# BPW5011-Digital-Wing.net
KiCad netlist of a schematic drawn in EAGLE
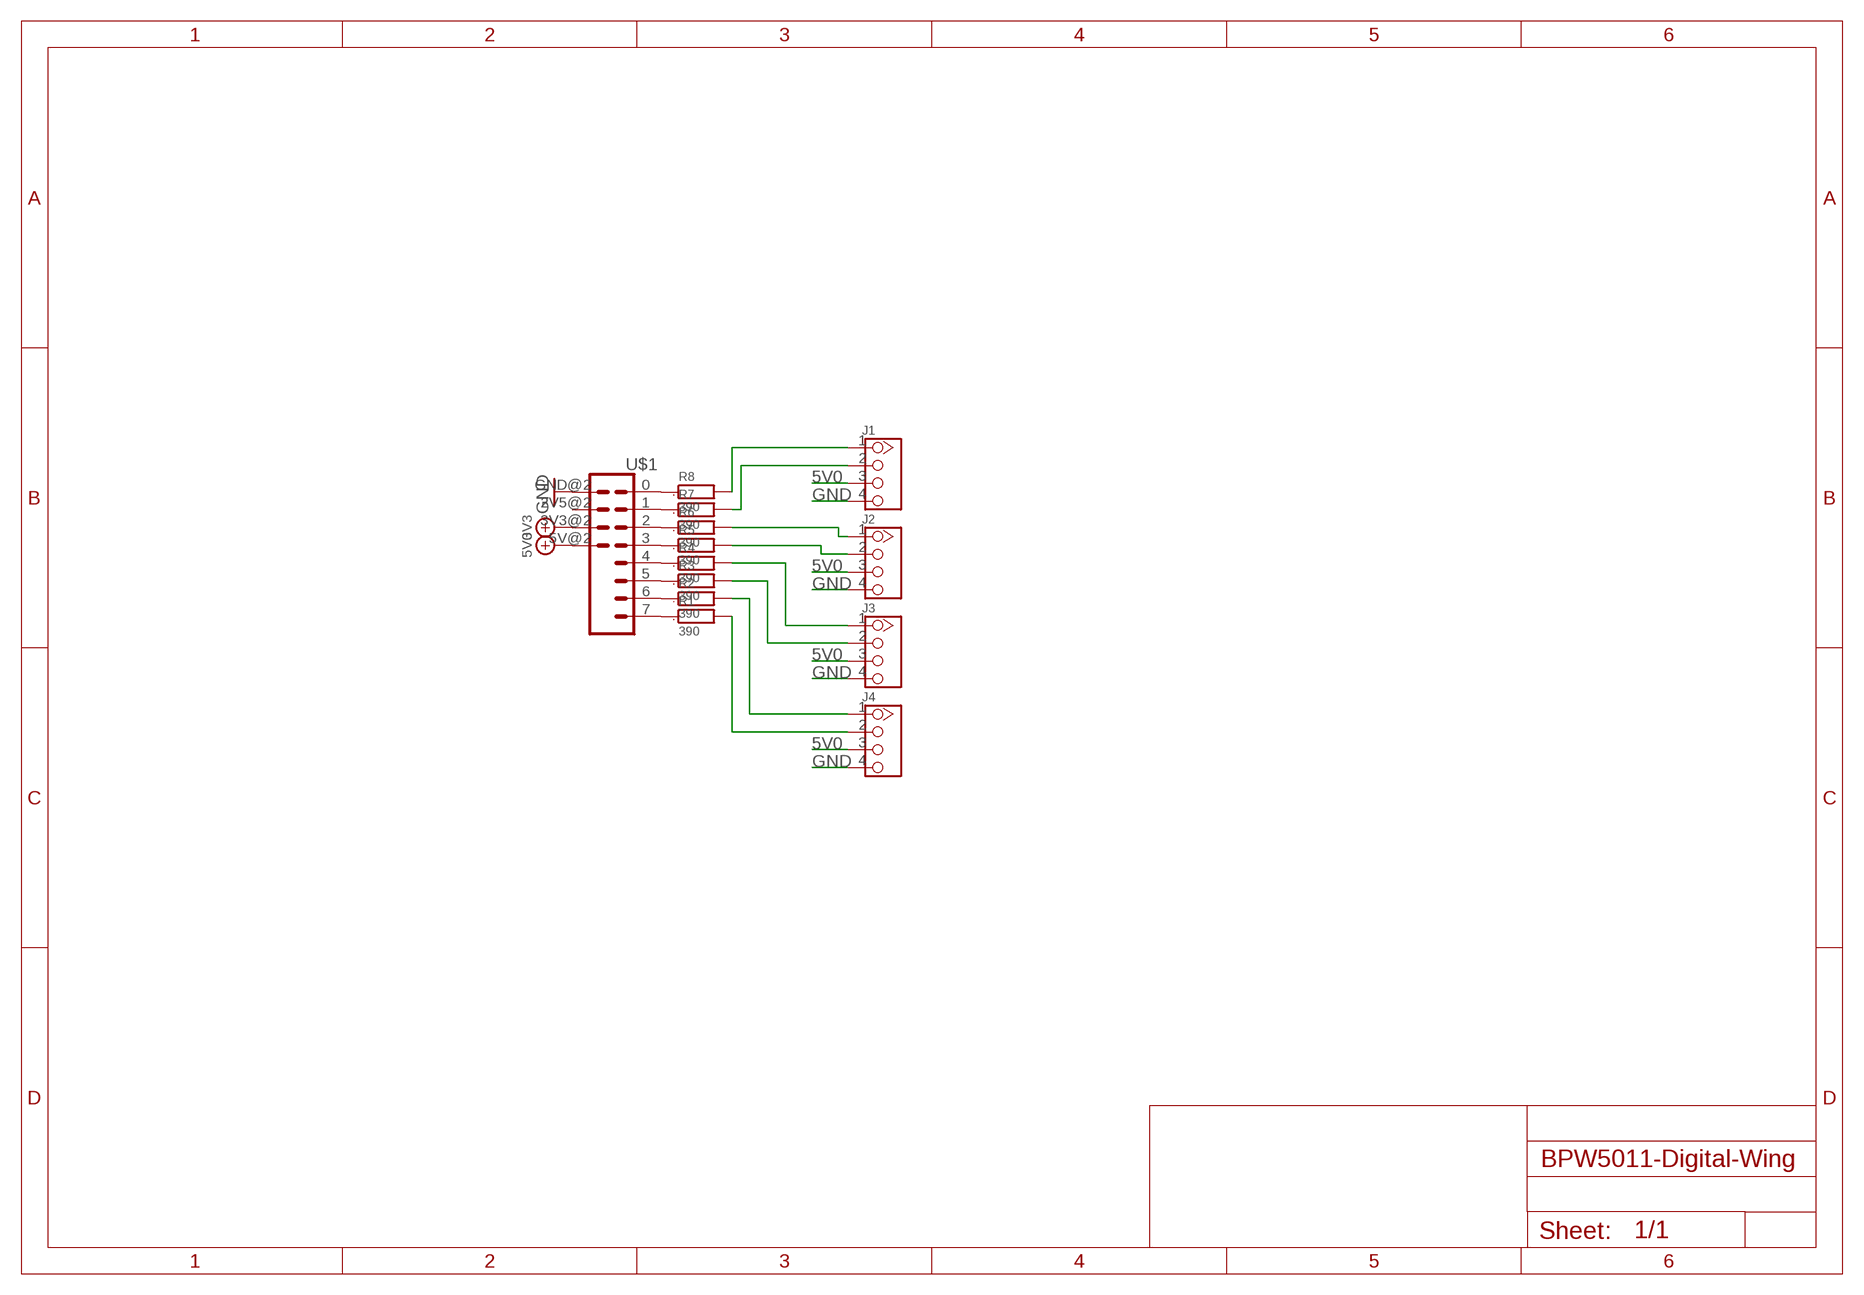
[diagram p0: schematic, sheet 1]

(export (version "E")
  (design (tool "Eeschema 10.0.6"))
  (components
    (comp (ref "J1")
      (value "CONNECTOR_TWIG-2.0-LEADED")
      (footprint "eagle-import:CONNECTOR_4P-LEADED-2.0")
      (libsource (lib "eagle-import") (part "CONNECTOR_TWIG-2.0-LEADED"))
    )
    (comp (ref "J2")
      (value "CONNECTOR_TWIG-2.0-LEADED")
      (footprint "eagle-import:CONNECTOR_4P-LEADED-2.0")
      (libsource (lib "eagle-import") (part "CONNECTOR_TWIG-2.0-LEADED"))
    )
    (comp (ref "J3")
      (value "CONNECTOR_TWIG-2.0-LEADED")
      (footprint "eagle-import:CONNECTOR_4P-LEADED-2.0")
      (libsource (lib "eagle-import") (part "CONNECTOR_TWIG-2.0-LEADED"))
    )
    (comp (ref "J4")
      (value "CONNECTOR_TWIG-2.0-LEADED")
      (footprint "eagle-import:CONNECTOR_4P-LEADED-2.0")
      (libsource (lib "eagle-import") (part "CONNECTOR_TWIG-2.0-LEADED"))
    )
    (comp (ref "R1")
      (value "390")
      (footprint "eagle-import:0805")
      (libsource (lib "eagle-import") (part "R0805"))
    )
    (comp (ref "R2")
      (value "390")
      (footprint "eagle-import:0805")
      (libsource (lib "eagle-import") (part "R0805"))
    )
    (comp (ref "R3")
      (value "390")
      (footprint "eagle-import:0805")
      (libsource (lib "eagle-import") (part "R0805"))
    )
    (comp (ref "R4")
      (value "390")
      (footprint "eagle-import:0805")
      (libsource (lib "eagle-import") (part "R0805"))
    )
    (comp (ref "R5")
      (value "390")
      (footprint "eagle-import:0805")
      (libsource (lib "eagle-import") (part "R0805"))
    )
    (comp (ref "R6")
      (value "390")
      (footprint "eagle-import:0805")
      (libsource (lib "eagle-import") (part "R0805"))
    )
    (comp (ref "R7")
      (value "390")
      (footprint "eagle-import:0805")
      (libsource (lib "eagle-import") (part "R0805"))
    )
    (comp (ref "R8")
      (value "390")
      (footprint "eagle-import:0805")
      (libsource (lib "eagle-import") (part "R0805"))
    )
    (comp (ref "U$1")
      (value "WING8WING8_NOHOLES")
      (footprint "eagle-import:WINGSIDE_8BIT_NOHOLES")
      (libsource (lib "eagle-import") (part "WING8WING8_NOHOLES"))
    )
  )
  (nets
    (net (code "1") (name "3V3") (class "Default")
      (node (ref "U$1") (pin "3V3@2") (pinfunction "3V3_3V3@2") (pintype "passive"))
    )
    (net (code "2") (name "5V0") (class "Default")
      (node (ref "J1") (pin "3") (pinfunction "3_3") (pintype "bidirectional"))
      (node (ref "J2") (pin "3") (pinfunction "3_3") (pintype "bidirectional"))
      (node (ref "J3") (pin "3") (pinfunction "3_3") (pintype "bidirectional"))
      (node (ref "J4") (pin "3") (pinfunction "3_3") (pintype "bidirectional"))
      (node (ref "U$1") (pin "5V@2") (pinfunction "5V_5V@2") (pintype "passive"))
    )
    (net (code "3") (name "GND") (class "Default")
      (node (ref "J1") (pin "4") (pinfunction "4_4") (pintype "bidirectional"))
      (node (ref "J2") (pin "4") (pinfunction "4_4") (pintype "bidirectional"))
      (node (ref "J3") (pin "4") (pinfunction "4_4") (pintype "bidirectional"))
      (node (ref "J4") (pin "4") (pinfunction "4_4") (pintype "bidirectional"))
      (node (ref "U$1") (pin "GND@2") (pinfunction "GND_GND@2") (pintype "passive"))
    )
    (net (code "4") (name "Net-(J1-Pad1)") (class "Default")
      (node (ref "J1") (pin "1") (pinfunction "1_1") (pintype "bidirectional"))
      (node (ref "R8") (pin "2") (pinfunction "2_2") (pintype "passive"))
    )
    (net (code "5") (name "Net-(J1-Pad2)") (class "Default")
      (node (ref "J1") (pin "2") (pinfunction "2_2") (pintype "bidirectional"))
      (node (ref "R7") (pin "2") (pinfunction "2_2") (pintype "passive"))
    )
    (net (code "6") (name "Net-(J2-Pad1)") (class "Default")
      (node (ref "J2") (pin "1") (pinfunction "1_1") (pintype "bidirectional"))
      (node (ref "R6") (pin "2") (pinfunction "2_2") (pintype "passive"))
    )
    (net (code "7") (name "Net-(J2-Pad2)") (class "Default")
      (node (ref "J2") (pin "2") (pinfunction "2_2") (pintype "bidirectional"))
      (node (ref "R5") (pin "2") (pinfunction "2_2") (pintype "passive"))
    )
    (net (code "8") (name "Net-(J3-Pad1)") (class "Default")
      (node (ref "J3") (pin "1") (pinfunction "1_1") (pintype "bidirectional"))
      (node (ref "R4") (pin "2") (pinfunction "2_2") (pintype "passive"))
    )
    (net (code "9") (name "Net-(J3-Pad2)") (class "Default")
      (node (ref "J3") (pin "2") (pinfunction "2_2") (pintype "bidirectional"))
      (node (ref "R3") (pin "2") (pinfunction "2_2") (pintype "passive"))
    )
    (net (code "10") (name "Net-(J4-Pad1)") (class "Default")
      (node (ref "J4") (pin "1") (pinfunction "1_1") (pintype "bidirectional"))
      (node (ref "R2") (pin "2") (pinfunction "2_2") (pintype "passive"))
    )
    (net (code "11") (name "Net-(J4-Pad2)") (class "Default")
      (node (ref "J4") (pin "2") (pinfunction "2_2") (pintype "bidirectional"))
      (node (ref "R1") (pin "2") (pinfunction "2_2") (pintype "passive"))
    )
    (net (code "12") (name "Net-(U$1-1)") (class "Default")
      (node (ref "R8") (pin "1") (pinfunction "1_1") (pintype "passive"))
      (node (ref "U$1") (pin "0") (pinfunction "1_0") (pintype "passive"))
    )
    (net (code "13") (name "Net-(U$1-2)") (class "Default")
      (node (ref "R7") (pin "1") (pinfunction "1_1") (pintype "passive"))
      (node (ref "U$1") (pin "1") (pinfunction "2_1") (pintype "passive"))
    )
    (net (code "14") (name "Net-(U$1-3)") (class "Default")
      (node (ref "R6") (pin "1") (pinfunction "1_1") (pintype "passive"))
      (node (ref "U$1") (pin "2") (pinfunction "3_2") (pintype "passive"))
    )
    (net (code "15") (name "Net-(U$1-4)") (class "Default")
      (node (ref "R5") (pin "1") (pinfunction "1_1") (pintype "passive"))
      (node (ref "U$1") (pin "3") (pinfunction "4_3") (pintype "passive"))
    )
    (net (code "16") (name "Net-(U$1-5)") (class "Default")
      (node (ref "R4") (pin "1") (pinfunction "1_1") (pintype "passive"))
      (node (ref "U$1") (pin "4") (pinfunction "5_4") (pintype "passive"))
    )
    (net (code "17") (name "Net-(U$1-6)") (class "Default")
      (node (ref "R3") (pin "1") (pinfunction "1_1") (pintype "passive"))
      (node (ref "U$1") (pin "5") (pinfunction "6_5") (pintype "passive"))
    )
    (net (code "18") (name "Net-(U$1-7)") (class "Default")
      (node (ref "R2") (pin "1") (pinfunction "1_1") (pintype "passive"))
      (node (ref "U$1") (pin "6") (pinfunction "7_6") (pintype "passive"))
    )
    (net (code "19") (name "Net-(U$1-8)") (class "Default")
      (node (ref "R1") (pin "1") (pinfunction "1_1") (pintype "passive"))
      (node (ref "U$1") (pin "7") (pinfunction "8_7") (pintype "passive"))
    )
    (net (code "20") (name "unconnected-(U$1-2V5-Pad2V5@2)") (class "Default")
      (node (ref "U$1") (pin "2V5@2") (pinfunction "2V5_2V5@2") (pintype "passive"))
    )
  )
)
